# Sheet1.net
KiCad netlist of a schematic drawn in Altium Designer
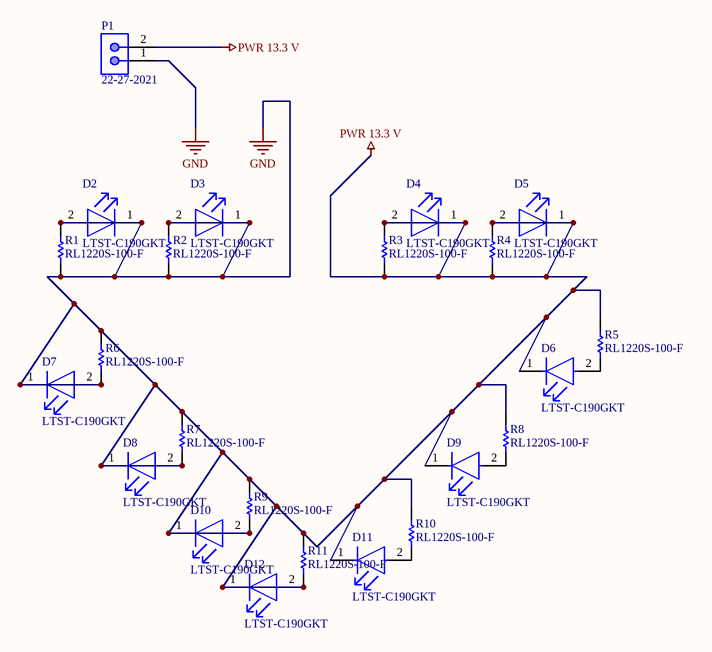
[diagram p0: Sheet1.SchDoc]

(export (version "E")
  (design (tool "Eeschema 10.0.6"))
  (components
    (comp (ref "D2")
      (value "LTST-C190GKT")
      (footprint "FP-LTST-C190GKT-MFG")
      (description "LED GREEN CLEAR CHIP SMD")
      (fields (field (name "VOLTAGE") "2V"))
      (libsource (lib "Altium Content Vault") (part "8706943c75ba83719d021d2fdc84c58"))
    )
    (comp (ref "D3")
      (value "LTST-C190GKT")
      (footprint "FP-LTST-C190GKT-MFG")
      (description "LED GREEN CLEAR CHIP SMD")
      (fields (field (name "VOLTAGE") "2V"))
      (libsource (lib "Altium Content Vault") (part "8706943c75ba83719d021d2fdc84c58"))
    )
    (comp (ref "D4")
      (value "LTST-C190GKT")
      (footprint "FP-LTST-C190GKT-MFG")
      (description "LED GREEN CLEAR CHIP SMD")
      (fields (field (name "VOLTAGE") "2V"))
      (libsource (lib "Altium Content Vault") (part "8706943c75ba83719d021d2fdc84c58"))
    )
    (comp (ref "D5")
      (value "LTST-C190GKT")
      (footprint "FP-LTST-C190GKT-MFG")
      (description "LED GREEN CLEAR CHIP SMD")
      (fields (field (name "VOLTAGE") "2V"))
      (libsource (lib "Altium Content Vault") (part "8706943c75ba83719d021d2fdc84c58"))
    )
    (comp (ref "D6")
      (value "LTST-C190GKT")
      (footprint "FP-LTST-C190GKT-MFG")
      (description "LED GREEN CLEAR CHIP SMD")
      (fields (field (name "VOLTAGE") "2V"))
      (libsource (lib "Altium Content Vault") (part "8706943c75ba83719d021d2fdc84c58"))
    )
    (comp (ref "D7")
      (value "LTST-C190GKT")
      (footprint "FP-LTST-C190GKT-MFG")
      (description "LED GREEN CLEAR CHIP SMD")
      (fields (field (name "VOLTAGE") "2V"))
      (libsource (lib "Altium Content Vault") (part "8706943c75ba83719d021d2fdc84c58"))
    )
    (comp (ref "D8")
      (value "LTST-C190GKT")
      (footprint "FP-LTST-C190GKT-MFG")
      (description "LED GREEN CLEAR CHIP SMD")
      (fields (field (name "VOLTAGE") "2V"))
      (libsource (lib "Altium Content Vault") (part "8706943c75ba83719d021d2fdc84c58"))
    )
    (comp (ref "D9")
      (value "LTST-C190GKT")
      (footprint "FP-LTST-C190GKT-MFG")
      (description "LED GREEN CLEAR CHIP SMD")
      (fields (field (name "VOLTAGE") "2V"))
      (libsource (lib "Altium Content Vault") (part "8706943c75ba83719d021d2fdc84c58"))
    )
    (comp (ref "D10")
      (value "LTST-C190GKT")
      (footprint "FP-LTST-C190GKT-MFG")
      (description "LED GREEN CLEAR CHIP SMD")
      (fields (field (name "VOLTAGE") "2V"))
      (libsource (lib "Altium Content Vault") (part "8706943c75ba83719d021d2fdc84c58"))
    )
    (comp (ref "D11")
      (value "LTST-C190GKT")
      (footprint "FP-LTST-C190GKT-MFG")
      (description "LED GREEN CLEAR CHIP SMD")
      (fields (field (name "VOLTAGE") "2V"))
      (libsource (lib "Altium Content Vault") (part "8706943c75ba83719d021d2fdc84c58"))
    )
    (comp (ref "D12")
      (value "LTST-C190GKT")
      (footprint "FP-LTST-C190GKT-MFG")
      (description "LED GREEN CLEAR CHIP SMD")
      (fields (field (name "VOLTAGE") "2V"))
      (libsource (lib "Altium Content Vault") (part "8706943c75ba83719d021d2fdc84c58"))
    )
    (comp (ref "P1")
      (value "22-27-2021")
      (footprint "MOLX-22-27-2021_V")
      (fields (field (name "MANUFACTURER") "Molex") (field (name "PARTNUMBER") "0022272021"))
      (libsource (lib "Altium Content Vault") (part "CN-1P-M-R2"))
    )
    (comp (ref "R1")
      (value "RL1220S-100-F")
      (footprint "RESC2013X50X40ML20T20")
      (fields (field (name "MANUFACTURER") "Susumu"))
      (libsource (lib "Altium Content Vault") (part "RES"))
    )
    (comp (ref "R2")
      (value "RL1220S-100-F")
      (footprint "RESC2013X50X40ML20T20")
      (fields (field (name "MANUFACTURER") "Susumu"))
      (libsource (lib "Altium Content Vault") (part "RES"))
    )
    (comp (ref "R3")
      (value "RL1220S-100-F")
      (footprint "RESC2013X50X40ML20T20")
      (fields (field (name "MANUFACTURER") "Susumu"))
      (libsource (lib "Altium Content Vault") (part "RES"))
    )
    (comp (ref "R4")
      (value "RL1220S-100-F")
      (footprint "RESC2013X50X40ML20T20")
      (fields (field (name "MANUFACTURER") "Susumu"))
      (libsource (lib "Altium Content Vault") (part "RES"))
    )
    (comp (ref "R5")
      (value "RL1220S-100-F")
      (footprint "RESC2013X50X40ML20T20")
      (fields (field (name "MANUFACTURER") "Susumu"))
      (libsource (lib "Altium Content Vault") (part "RES"))
    )
    (comp (ref "R6")
      (value "RL1220S-100-F")
      (footprint "RESC2013X50X40ML20T20")
      (fields (field (name "MANUFACTURER") "Susumu"))
      (libsource (lib "Altium Content Vault") (part "RES"))
    )
    (comp (ref "R7")
      (value "RL1220S-100-F")
      (footprint "RESC2013X50X40ML20T20")
      (fields (field (name "MANUFACTURER") "Susumu"))
      (libsource (lib "Altium Content Vault") (part "RES"))
    )
    (comp (ref "R8")
      (value "RL1220S-100-F")
      (footprint "RESC2013X50X40ML20T20")
      (fields (field (name "MANUFACTURER") "Susumu"))
      (libsource (lib "Altium Content Vault") (part "RES"))
    )
    (comp (ref "R9")
      (value "RL1220S-100-F")
      (footprint "RESC2013X50X40ML20T20")
      (fields (field (name "MANUFACTURER") "Susumu"))
      (libsource (lib "Altium Content Vault") (part "RES"))
    )
    (comp (ref "R10")
      (value "RL1220S-100-F")
      (footprint "RESC2013X50X40ML20T20")
      (fields (field (name "MANUFACTURER") "Susumu"))
      (libsource (lib "Altium Content Vault") (part "RES"))
    )
    (comp (ref "R11")
      (value "RL1220S-100-F")
      (footprint "RESC2013X50X40ML20T20")
      (fields (field (name "MANUFACTURER") "Susumu"))
      (libsource (lib "Altium Content Vault") (part "RES"))
    )
  )
  (nets
    (net (code "1") (name "GND") (class "Default")
      (node (ref "D10") (pin "1") (pinfunction "C_1") (pintype "passive"))
      (node (ref "D10") (pin "2") (pinfunction "A_2") (pintype "passive"))
      (node (ref "D11") (pin "1") (pinfunction "C_1") (pintype "passive"))
      (node (ref "D12") (pin "1") (pinfunction "C_1") (pintype "passive"))
      (node (ref "D12") (pin "2") (pinfunction "A_2") (pintype "passive"))
      (node (ref "D2") (pin "1") (pinfunction "C_1") (pintype "passive"))
      (node (ref "D2") (pin "2") (pinfunction "A_2") (pintype "passive"))
      (node (ref "D3") (pin "1") (pinfunction "C_1") (pintype "passive"))
      (node (ref "D3") (pin "2") (pinfunction "A_2") (pintype "passive"))
      (node (ref "D4") (pin "1") (pinfunction "C_1") (pintype "passive"))
      (node (ref "D4") (pin "2") (pinfunction "A_2") (pintype "passive"))
      (node (ref "D5") (pin "1") (pinfunction "C_1") (pintype "passive"))
      (node (ref "D5") (pin "2") (pinfunction "A_2") (pintype "passive"))
      (node (ref "D6") (pin "1") (pinfunction "C_1") (pintype "passive"))
      (node (ref "D7") (pin "1") (pinfunction "C_1") (pintype "passive"))
      (node (ref "D7") (pin "2") (pinfunction "A_2") (pintype "passive"))
      (node (ref "D8") (pin "1") (pinfunction "C_1") (pintype "passive"))
      (node (ref "D8") (pin "2") (pinfunction "A_2") (pintype "passive"))
      (node (ref "D9") (pin "1") (pinfunction "C_1") (pintype "passive"))
      (node (ref "P1") (pin "1") (pinfunction "1_1") (pintype "passive"))
      (node (ref "P1") (pin "2") (pinfunction "2_2") (pintype "passive"))
      (node (ref "R1") (pin "1") (pinfunction "1_1") (pintype "passive"))
      (node (ref "R1") (pin "2") (pinfunction "2_2") (pintype "passive"))
      (node (ref "R10") (pin "1") (pinfunction "1_1") (pintype "passive"))
      (node (ref "R11") (pin "1") (pinfunction "1_1") (pintype "passive"))
      (node (ref "R11") (pin "2") (pinfunction "2_2") (pintype "passive"))
      (node (ref "R2") (pin "1") (pinfunction "1_1") (pintype "passive"))
      (node (ref "R2") (pin "2") (pinfunction "2_2") (pintype "passive"))
      (node (ref "R3") (pin "1") (pinfunction "1_1") (pintype "passive"))
      (node (ref "R3") (pin "2") (pinfunction "2_2") (pintype "passive"))
      (node (ref "R4") (pin "1") (pinfunction "1_1") (pintype "passive"))
      (node (ref "R4") (pin "2") (pinfunction "2_2") (pintype "passive"))
      (node (ref "R5") (pin "1") (pinfunction "1_1") (pintype "passive"))
      (node (ref "R6") (pin "1") (pinfunction "1_1") (pintype "passive"))
      (node (ref "R6") (pin "2") (pinfunction "2_2") (pintype "passive"))
      (node (ref "R7") (pin "1") (pinfunction "1_1") (pintype "passive"))
      (node (ref "R7") (pin "2") (pinfunction "2_2") (pintype "passive"))
      (node (ref "R8") (pin "1") (pinfunction "1_1") (pintype "passive"))
      (node (ref "R9") (pin "1") (pinfunction "1_1") (pintype "passive"))
      (node (ref "R9") (pin "2") (pinfunction "2_2") (pintype "passive"))
    )
    (net (code "2") (name "Net-(D6-A)") (class "Default")
      (node (ref "D6") (pin "2") (pinfunction "A_2") (pintype "passive"))
      (node (ref "R5") (pin "2") (pinfunction "2_2") (pintype "passive"))
    )
    (net (code "3") (name "Net-(D9-A)") (class "Default")
      (node (ref "D9") (pin "2") (pinfunction "A_2") (pintype "passive"))
      (node (ref "R8") (pin "2") (pinfunction "2_2") (pintype "passive"))
    )
    (net (code "4") (name "Net-(D11-A)") (class "Default")
      (node (ref "D11") (pin "2") (pinfunction "A_2") (pintype "passive"))
      (node (ref "R10") (pin "2") (pinfunction "2_2") (pintype "passive"))
    )
  )
)
